# Power_Amplifier_BTL_90_Watt_TDA2004.net
KiCad netlist of a schematic drawn in EAGLE
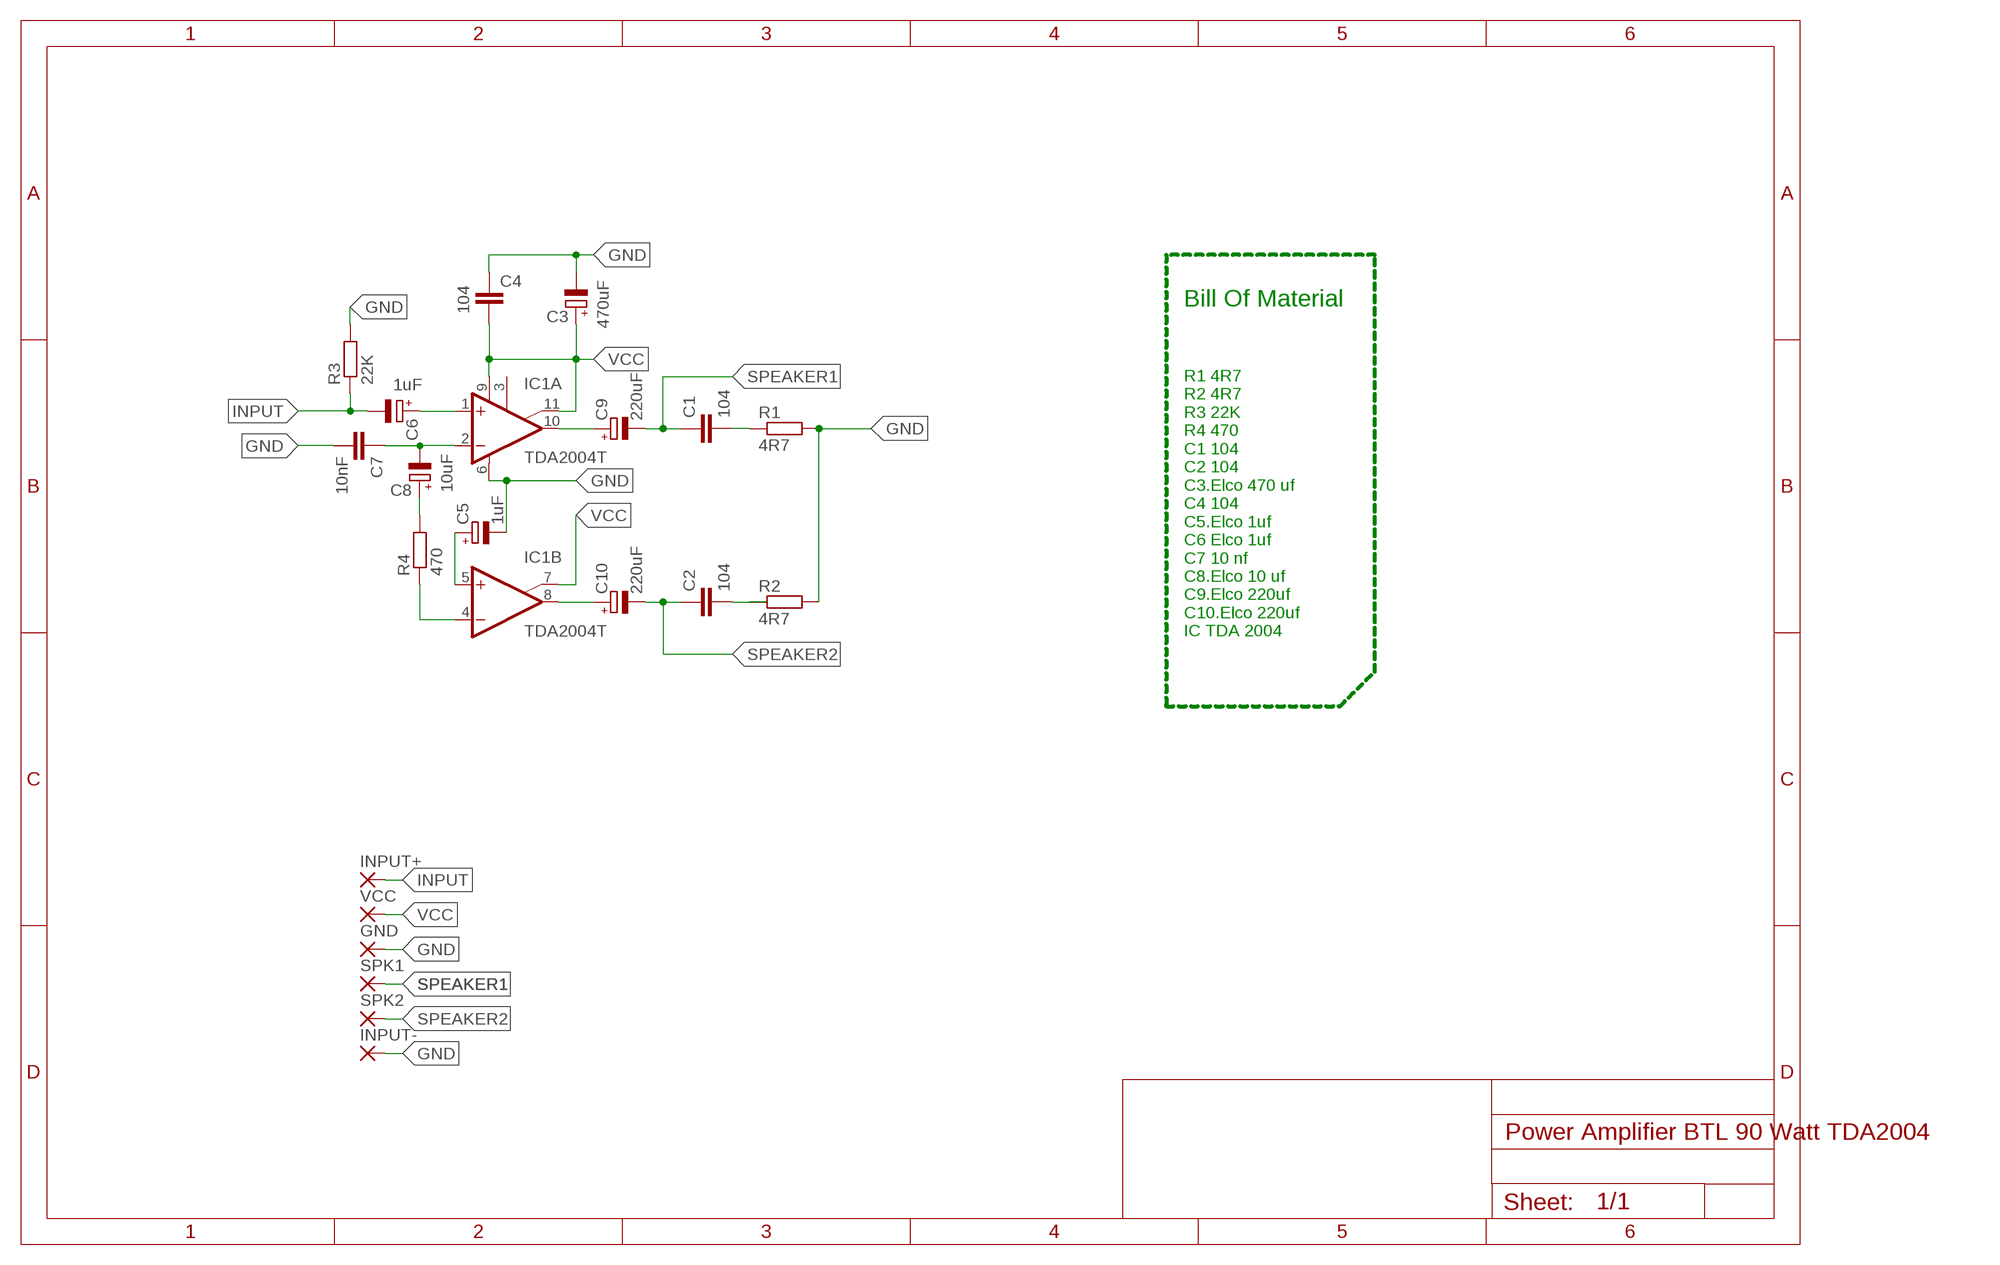
[diagram p0: schematic, sheet 1]

(export (version "E")
  (design (tool "Eeschema 10.0.6"))
  (components
    (comp (ref "C1")
      (value "104")
      (footprint "eagle-import:C025-025X050")
      (libsource (lib "eagle-import") (part "C-EU025-025X050"))
    )
    (comp (ref "C2")
      (value "104")
      (footprint "eagle-import:C025-025X050")
      (libsource (lib "eagle-import") (part "C-EU025-025X050"))
    )
    (comp (ref "C3")
      (value "470uF")
      (footprint "eagle-import:E1,8-4")
      (libsource (lib "eagle-import") (part "CPOL-EUE1.8-4"))
    )
    (comp (ref "C4")
      (value "104")
      (footprint "eagle-import:C025-025X050")
      (libsource (lib "eagle-import") (part "C-EU025-025X050"))
    )
    (comp (ref "C5")
      (value "1uF")
      (footprint "eagle-import:E1,8-4")
      (libsource (lib "eagle-import") (part "CPOL-EUE1.8-4"))
    )
    (comp (ref "C6")
      (value "1uF")
      (footprint "eagle-import:E1,8-4")
      (libsource (lib "eagle-import") (part "CPOL-EUE1.8-4"))
    )
    (comp (ref "C7")
      (value "10nF")
      (footprint "eagle-import:C025-025X050")
      (libsource (lib "eagle-import") (part "C-EU025-025X050"))
    )
    (comp (ref "C8")
      (value "10uF")
      (footprint "eagle-import:E1,8-4")
      (libsource (lib "eagle-import") (part "CPOL-EUE1.8-4"))
    )
    (comp (ref "C9")
      (value "220uF")
      (footprint "eagle-import:E1,8-4")
      (libsource (lib "eagle-import") (part "CPOL-EUE1.8-4"))
    )
    (comp (ref "C10")
      (value "220uF")
      (footprint "eagle-import:E1,8-4")
      (libsource (lib "eagle-import") (part "CPOL-EUE1.8-4"))
    )
    (comp (ref "GND")
      (value "1,6/0,8")
      (footprint "eagle-import:1,6_0,8")
      (libsource (lib "eagle-import") (part "1,6/0,8"))
    )
    (comp (ref "IC1")
      (value "TDA2004T")
      (footprint "eagle-import:SIP11")
      (fields (field (name "MF") "STMicroelectronics") (field (name "MP") "TDA2004"))
      (libsource (lib "eagle-import") (part "TDA2004T"))
    )
    (comp (ref "INPUT+")
      (value "1,6/0,8")
      (footprint "eagle-import:1,6_0,8")
      (libsource (lib "eagle-import") (part "1,6/0,8"))
    )
    (comp (ref "INPUT-")
      (value "1,6/0,8")
      (footprint "eagle-import:1,6_0,8")
      (libsource (lib "eagle-import") (part "1,6/0,8"))
    )
    (comp (ref "R1")
      (value "4R7")
      (footprint "eagle-import:0204_7")
      (libsource (lib "eagle-import") (part "R-EU_0204/7"))
    )
    (comp (ref "R2")
      (value "4R7")
      (footprint "eagle-import:0204_7")
      (libsource (lib "eagle-import") (part "R-EU_0204/7"))
    )
    (comp (ref "R3")
      (value "22K")
      (footprint "eagle-import:0204_7")
      (libsource (lib "eagle-import") (part "R-EU_0204/7"))
    )
    (comp (ref "R4")
      (value "470")
      (footprint "eagle-import:0204_7")
      (libsource (lib "eagle-import") (part "R-EU_0204/7"))
    )
    (comp (ref "SPK1")
      (value "1,6/0,8")
      (footprint "eagle-import:1,6_0,8")
      (libsource (lib "eagle-import") (part "1,6/0,8"))
    )
    (comp (ref "SPK2")
      (value "1,6/0,8")
      (footprint "eagle-import:1,6_0,8")
      (libsource (lib "eagle-import") (part "1,6/0,8"))
    )
    (comp (ref "VCC")
      (value "1,6/0,8")
      (footprint "eagle-import:1,6_0,8")
      (libsource (lib "eagle-import") (part "1,6/0,8"))
    )
  )
  (nets
    (net (code "1") (name "GND") (class "Default")
      (node (ref "C3") (pin "-") (pinfunction "-_-") (pintype "passive"))
      (node (ref "C4") (pin "1") (pinfunction "1_1") (pintype "passive"))
      (node (ref "C5") (pin "-") (pinfunction "-_-") (pintype "passive"))
      (node (ref "C7") (pin "2") (pinfunction "2_2") (pintype "passive"))
      (node (ref "GND") (pin "1") (pinfunction "P_1") (pintype "passive"))
      (node (ref "IC1") (pin "6") (pinfunction "GND_6") (pintype "power_in"))
      (node (ref "INPUT-") (pin "1") (pinfunction "P_1") (pintype "passive"))
      (node (ref "R1") (pin "2") (pinfunction "2_2") (pintype "passive"))
      (node (ref "R2") (pin "2") (pinfunction "2_2") (pintype "passive"))
      (node (ref "R3") (pin "2") (pinfunction "2_2") (pintype "passive"))
    )
    (net (code "2") (name "INPUT") (class "Default")
      (node (ref "C6") (pin "-") (pinfunction "-_-") (pintype "passive"))
      (node (ref "INPUT+") (pin "1") (pinfunction "P_1") (pintype "passive"))
      (node (ref "R3") (pin "1") (pinfunction "1_1") (pintype "passive"))
    )
    (net (code "3") (name "Net-(C1-Pad2)") (class "Default")
      (node (ref "C1") (pin "2") (pinfunction "2_2") (pintype "passive"))
      (node (ref "R1") (pin "1") (pinfunction "1_1") (pintype "passive"))
    )
    (net (code "4") (name "Net-(C2-Pad2)") (class "Default")
      (node (ref "C2") (pin "2") (pinfunction "2_2") (pintype "passive"))
      (node (ref "R2") (pin "1") (pinfunction "1_1") (pintype "passive"))
    )
    (net (code "5") (name "Net-(C8-Pad+)") (class "Default")
      (node (ref "C8") (pin "+") (pinfunction "+_+") (pintype "passive"))
      (node (ref "R4") (pin "2") (pinfunction "2_2") (pintype "passive"))
    )
    (net (code "6") (name "Net-(IC1A-+IN)") (class "Default")
      (node (ref "C6") (pin "+") (pinfunction "+_+") (pintype "passive"))
      (node (ref "IC1") (pin "1") (pinfunction "+IN_1") (pintype "input"))
    )
    (net (code "7") (name "Net-(IC1A--IN)") (class "Default")
      (node (ref "C7") (pin "1") (pinfunction "1_1") (pintype "passive"))
      (node (ref "C8") (pin "-") (pinfunction "-_-") (pintype "passive"))
      (node (ref "IC1") (pin "2") (pinfunction "-IN_2") (pintype "input"))
    )
    (net (code "8") (name "Net-(IC1A-OUT)") (class "Default")
      (node (ref "C9") (pin "+") (pinfunction "+_+") (pintype "passive"))
      (node (ref "IC1") (pin "10") (pinfunction "OUT_10") (pintype "output"))
    )
    (net (code "9") (name "Net-(IC1B-+IN)") (class "Default")
      (node (ref "C5") (pin "+") (pinfunction "+_+") (pintype "passive"))
      (node (ref "IC1") (pin "5") (pinfunction "+IN_5") (pintype "input"))
    )
    (net (code "10") (name "Net-(IC1B--IN)") (class "Default")
      (node (ref "IC1") (pin "4") (pinfunction "-IN_4") (pintype "input"))
      (node (ref "R4") (pin "1") (pinfunction "1_1") (pintype "passive"))
    )
    (net (code "11") (name "Net-(IC1B-OUT)") (class "Default")
      (node (ref "C10") (pin "+") (pinfunction "+_+") (pintype "passive"))
      (node (ref "IC1") (pin "8") (pinfunction "OUT_8") (pintype "output"))
    )
    (net (code "12") (name "SPEAKER1") (class "Default")
      (node (ref "C1") (pin "1") (pinfunction "1_1") (pintype "passive"))
      (node (ref "C9") (pin "-") (pinfunction "-_-") (pintype "passive"))
      (node (ref "SPK1") (pin "1") (pinfunction "P_1") (pintype "passive"))
    )
    (net (code "13") (name "SPEAKER2") (class "Default")
      (node (ref "C10") (pin "-") (pinfunction "-_-") (pintype "passive"))
      (node (ref "C2") (pin "1") (pinfunction "1_1") (pintype "passive"))
      (node (ref "SPK2") (pin "1") (pinfunction "P_1") (pintype "passive"))
    )
    (net (code "14") (name "VCC") (class "Default")
      (node (ref "C3") (pin "+") (pinfunction "+_+") (pintype "passive"))
      (node (ref "C4") (pin "2") (pinfunction "2_2") (pintype "passive"))
      (node (ref "IC1") (pin "11") (pinfunction "BTSP_11") (pintype "passive"))
      (node (ref "IC1") (pin "7") (pinfunction "BTSP_7") (pintype "passive"))
      (node (ref "IC1") (pin "9") (pinfunction "V+_9") (pintype "power_in"))
      (node (ref "VCC") (pin "1") (pinfunction "P_1") (pintype "passive"))
    )
    (net (code "15") (name "unconnected-(IC1A-SVRR-Pad3)") (class "Default")
      (node (ref "IC1") (pin "3") (pinfunction "SVRR_3") (pintype "passive"))
    )
  )
)
